# icm20948.net
KiCad netlist of a schematic drawn in EasyEDA Pro
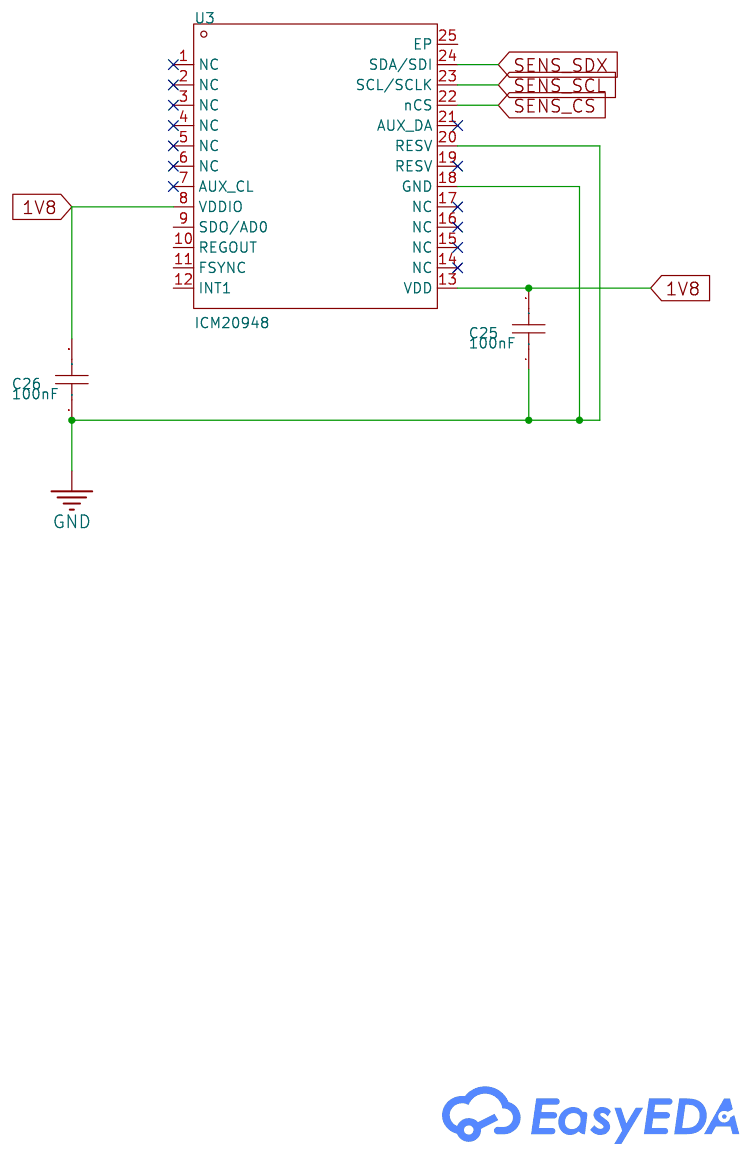
[diagram p0: schematic sheet]

(export (version "E")
  (design (tool "Eeschema 10.0.6"))
  (components
    (comp (ref "C25")
      (value "100nF")
      (footprint "easyedapro:C0201")
      (description "Capacitance:100nF Tolerance:±10% Tolerance:±10% Voltage Rating:10V Temperature Coefficient:X5R")
      (fields
        (field (name "Manufacturer Part") "C0201X5R104K100NTA")
        (field (name "Manufacturer") "EYANG(宇阳科技)")
      )
      (libsource (lib "easyedapro") (part "C0201X5R104K100NTA"))
    )
    (comp (ref "C26")
      (value "100nF")
      (footprint "easyedapro:C0201")
      (description "Capacitance:100nF Tolerance:±10% Tolerance:±10% Voltage Rating:10V Temperature Coefficient:X5R")
      (fields
        (field (name "Manufacturer Part") "C0201X5R104K100NTA")
        (field (name "Manufacturer") "EYANG(宇阳科技)")
      )
      (libsource (lib "easyedapro") (part "C0201X5R104K100NTA"))
    )
    (comp (ref "U3")
      (value "ICM20948")
      (footprint "easyedapro:QFN-24_L3.0-W3.0-P0.40-BL-EP")
      (libsource (lib "easyedapro") (part "ICM20948"))
    )
  )
  (nets
    (net (code "1") (name "1V8") (class "Default")
      (node (ref "C25") (pin "2") (pinfunction "2_2") (pintype "unspecified"))
      (node (ref "C26") (pin "2") (pinfunction "2_2") (pintype "unspecified"))
      (node (ref "U3") (pin "13") (pinfunction "VDD_13") (pintype "input"))
      (node (ref "U3") (pin "8") (pinfunction "VDDIO_8") (pintype "input"))
    )
    (net (code "2") (name "GND") (class "Default")
      (node (ref "C25") (pin "1") (pinfunction "1_1") (pintype "unspecified"))
      (node (ref "C26") (pin "1") (pinfunction "1_1") (pintype "unspecified"))
      (node (ref "U3") (pin "18") (pinfunction "GND_18") (pintype "input"))
      (node (ref "U3") (pin "20") (pinfunction "RESV_20") (pintype "input"))
    )
    (net (code "3") (name "SENS_CS") (class "Default")
      (node (ref "U3") (pin "22") (pinfunction "nCS_22") (pintype "input"))
    )
    (net (code "4") (name "SENS_SCL") (class "Default")
      (node (ref "U3") (pin "23") (pinfunction "SCL/SCLK_23") (pintype "input"))
    )
    (net (code "5") (name "SENS_SDX") (class "Default")
      (node (ref "U3") (pin "24") (pinfunction "SDA/SDI_24") (pintype "input"))
    )
    (net (code "6") (name "unconnected-(U3-AUX_CL-Pad7)") (class "Default")
      (node (ref "U3") (pin "7") (pinfunction "AUX_CL_7") (pintype "input+no_connect"))
    )
    (net (code "7") (name "unconnected-(U3-AUX_DA-Pad21)") (class "Default")
      (node (ref "U3") (pin "21") (pinfunction "AUX_DA_21") (pintype "input+no_connect"))
    )
    (net (code "8") (name "unconnected-(U3-EP-Pad25)") (class "Default")
      (node (ref "U3") (pin "25") (pinfunction "EP_25") (pintype "input"))
    )
    (net (code "9") (name "unconnected-(U3-FSYNC-Pad11)") (class "Default")
      (node (ref "U3") (pin "11") (pinfunction "FSYNC_11") (pintype "input"))
    )
    (net (code "10") (name "unconnected-(U3-INT1-Pad12)") (class "Default")
      (node (ref "U3") (pin "12") (pinfunction "INT1_12") (pintype "input"))
    )
    (net (code "11") (name "unconnected-(U3-NC-Pad1)") (class "Default")
      (node (ref "U3") (pin "1") (pinfunction "NC_1") (pintype "input+no_connect"))
    )
    (net (code "12") (name "unconnected-(U3-NC-Pad2)") (class "Default")
      (node (ref "U3") (pin "2") (pinfunction "NC_2") (pintype "input+no_connect"))
    )
    (net (code "13") (name "unconnected-(U3-NC-Pad3)") (class "Default")
      (node (ref "U3") (pin "3") (pinfunction "NC_3") (pintype "input+no_connect"))
    )
    (net (code "14") (name "unconnected-(U3-NC-Pad4)") (class "Default")
      (node (ref "U3") (pin "4") (pinfunction "NC_4") (pintype "input+no_connect"))
    )
    (net (code "15") (name "unconnected-(U3-NC-Pad5)") (class "Default")
      (node (ref "U3") (pin "5") (pinfunction "NC_5") (pintype "input+no_connect"))
    )
    (net (code "16") (name "unconnected-(U3-NC-Pad6)") (class "Default")
      (node (ref "U3") (pin "6") (pinfunction "NC_6") (pintype "input+no_connect"))
    )
    (net (code "17") (name "unconnected-(U3-NC-Pad14)") (class "Default")
      (node (ref "U3") (pin "14") (pinfunction "NC_14") (pintype "input+no_connect"))
    )
    (net (code "18") (name "unconnected-(U3-NC-Pad15)") (class "Default")
      (node (ref "U3") (pin "15") (pinfunction "NC_15") (pintype "input+no_connect"))
    )
    (net (code "19") (name "unconnected-(U3-NC-Pad16)") (class "Default")
      (node (ref "U3") (pin "16") (pinfunction "NC_16") (pintype "input+no_connect"))
    )
    (net (code "20") (name "unconnected-(U3-NC-Pad17)") (class "Default")
      (node (ref "U3") (pin "17") (pinfunction "NC_17") (pintype "input+no_connect"))
    )
    (net (code "21") (name "unconnected-(U3-REGOUT-Pad10)") (class "Default")
      (node (ref "U3") (pin "10") (pinfunction "REGOUT_10") (pintype "input"))
    )
    (net (code "22") (name "unconnected-(U3-RESV-Pad19)") (class "Default")
      (node (ref "U3") (pin "19") (pinfunction "RESV_19") (pintype "input+no_connect"))
    )
    (net (code "23") (name "unconnected-(U3-SDO{slash}AD0-Pad9)") (class "Default")
      (node (ref "U3") (pin "9") (pinfunction "SDO/AD0_9") (pintype "input"))
    )
  )
)
